# SL869-GL868-Cx.net
KiCad netlist of a schematic drawn in EAGLE
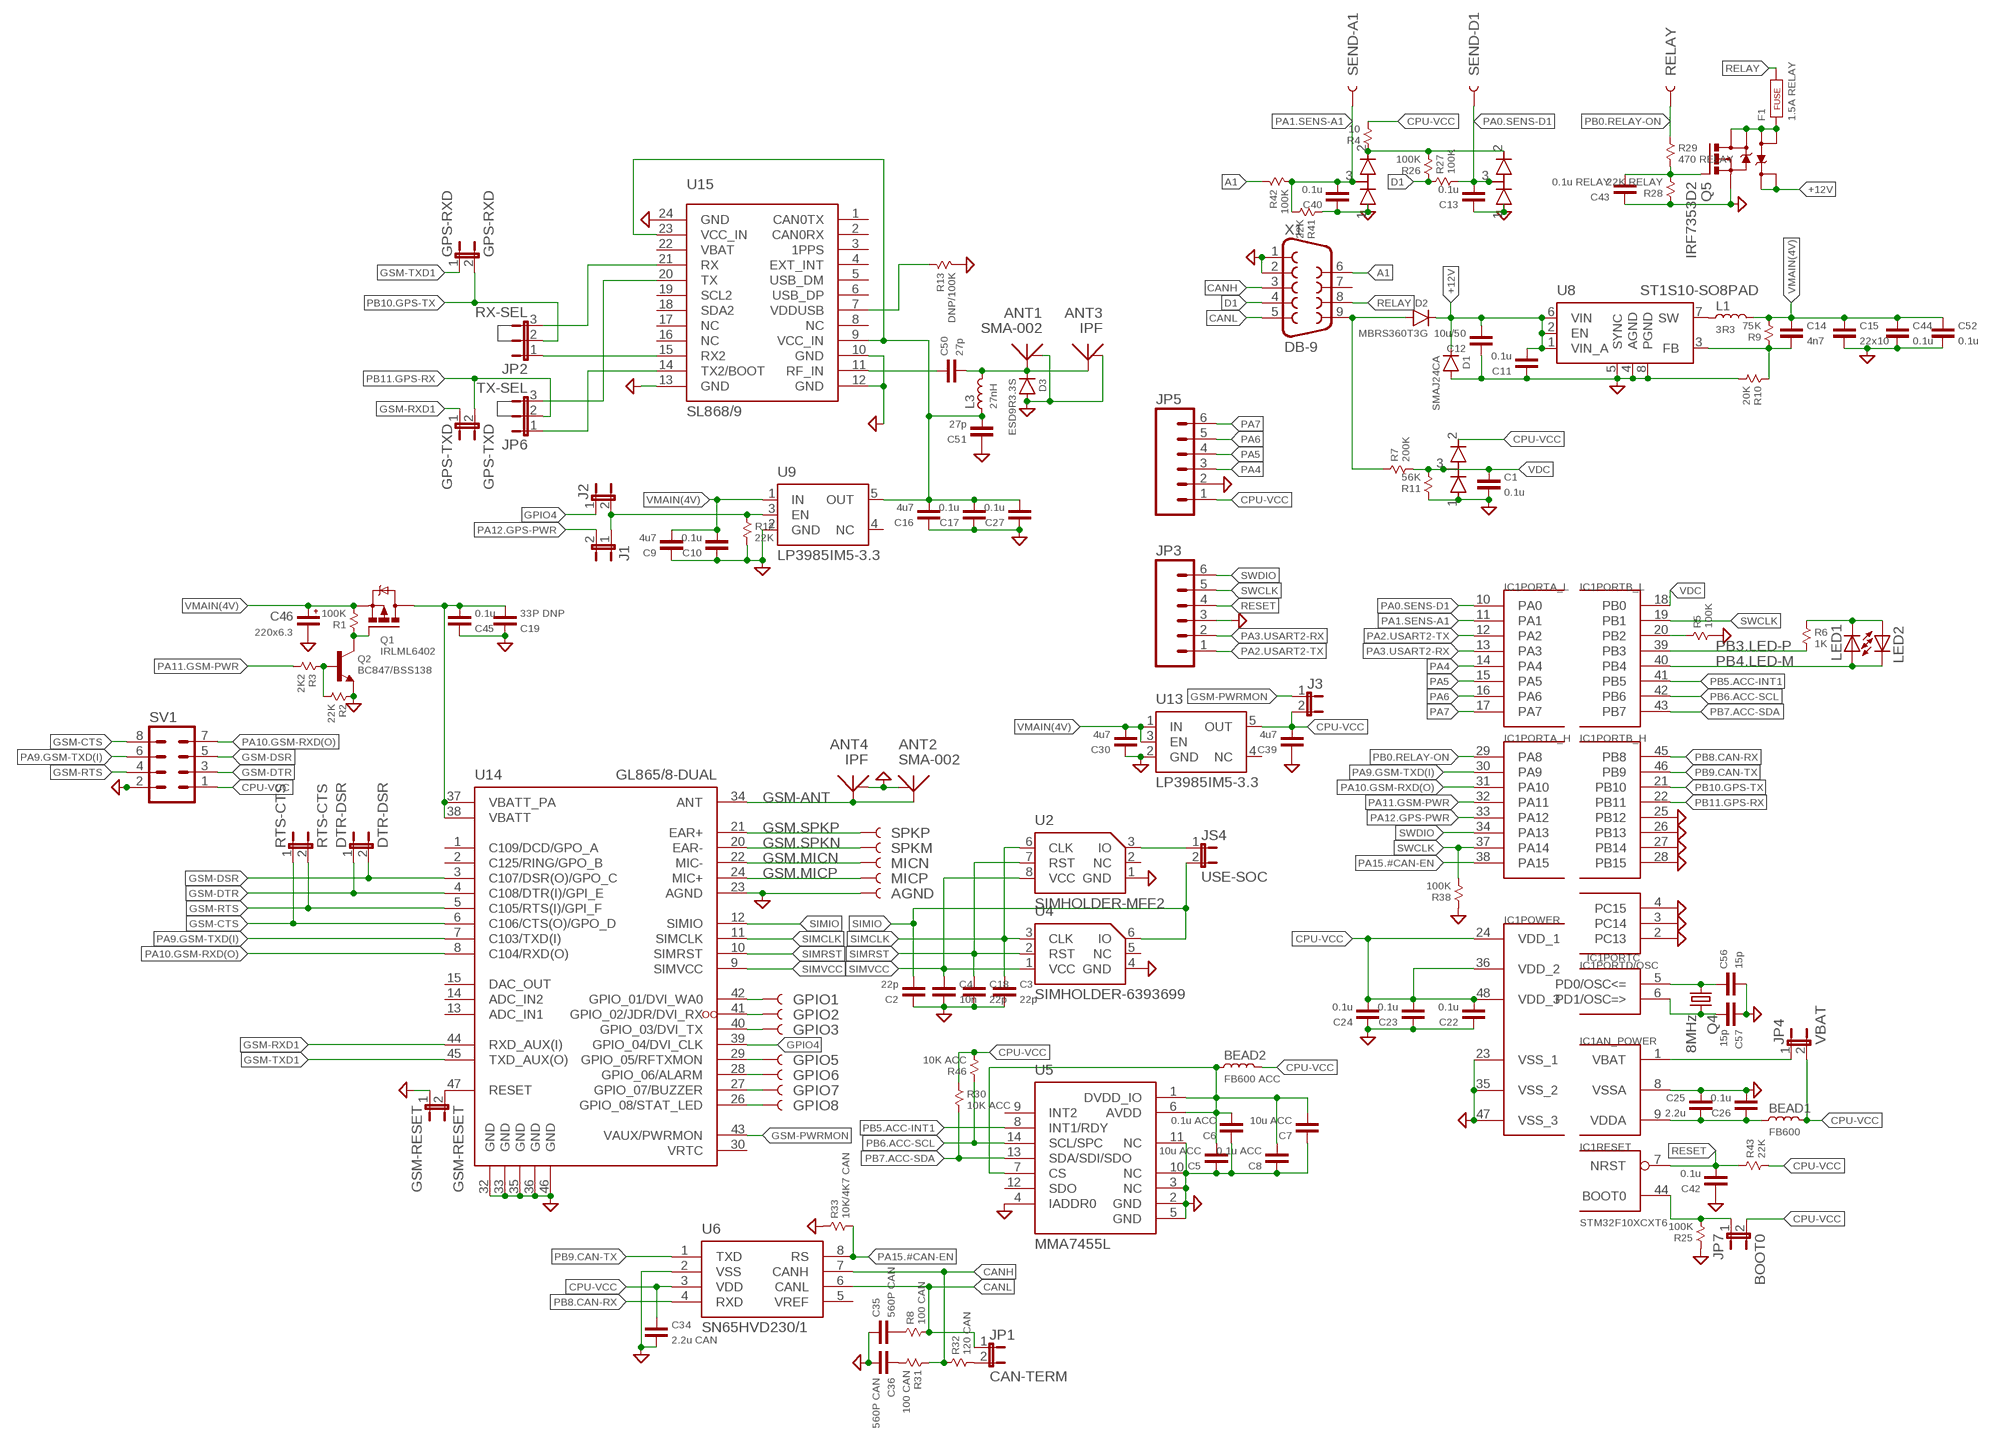
[diagram p0: schematic, sheet 1]

(export (version "E")
  (design (tool "Eeschema 10.0.6"))
  (components
    (comp (ref "AGND")
      (value "TEST-POINT1")
      (footprint "eagle-import:PAD.1X1")
      (libsource (lib "eagle-import") (part "TEST-POINT1"))
    )
    (comp (ref "ANT1")
      (value "SMA-002")
      (footprint "eagle-import:SMA-002")
      (libsource (lib "eagle-import") (part "ANTENNA-SMA-002"))
    )
    (comp (ref "ANT2")
      (value "SMA-002")
      (footprint "eagle-import:SMA-002")
      (libsource (lib "eagle-import") (part "ANTENNA-SMA-002"))
    )
    (comp (ref "ANT3")
      (value "IPF")
      (footprint "eagle-import:MM9329")
      (libsource (lib "eagle-import") (part "ANTENNA-IPF"))
    )
    (comp (ref "ANT4")
      (value "IPF")
      (footprint "eagle-import:MM9329")
      (libsource (lib "eagle-import") (part "ANTENNA-IPF"))
    )
    (comp (ref "BEAD1")
      (value "FB600")
      (footprint "eagle-import:0603")
      (libsource (lib "eagle-import") (part "INDUCTOR-0603"))
    )
    (comp (ref "BEAD2")
      (value "FB600 ACC")
      (footprint "eagle-import:0603")
      (libsource (lib "eagle-import") (part "INDUCTOR-0603"))
    )
    (comp (ref "C1")
      (value "0.1u")
      (footprint "eagle-import:0603")
      (libsource (lib "eagle-import") (part "CAP-0603"))
    )
    (comp (ref "C2")
      (value "22p")
      (footprint "eagle-import:0603")
      (libsource (lib "eagle-import") (part "CAP-0603"))
    )
    (comp (ref "C3")
      (value "22p")
      (footprint "eagle-import:0603")
      (libsource (lib "eagle-import") (part "CAP-0603"))
    )
    (comp (ref "C4")
      (value "10n")
      (footprint "eagle-import:0603")
      (libsource (lib "eagle-import") (part "CAP-0603"))
    )
    (comp (ref "C5")
      (value "10u ACC")
      (footprint "eagle-import:0603")
      (libsource (lib "eagle-import") (part "CAP-0603"))
    )
    (comp (ref "C6")
      (value "0.1u ACC")
      (footprint "eagle-import:0603")
      (libsource (lib "eagle-import") (part "CAP-0603"))
    )
    (comp (ref "C7")
      (value "10u ACC")
      (footprint "eagle-import:0603")
      (libsource (lib "eagle-import") (part "CAP-0603"))
    )
    (comp (ref "C8")
      (value "0.1u ACC")
      (footprint "eagle-import:0603")
      (libsource (lib "eagle-import") (part "CAP-0603"))
    )
    (comp (ref "C9")
      (value "4u7")
      (footprint "eagle-import:0603")
      (libsource (lib "eagle-import") (part "CAP-0603"))
    )
    (comp (ref "C10")
      (value "0.1u")
      (footprint "eagle-import:0603")
      (libsource (lib "eagle-import") (part "CAP-0603"))
    )
    (comp (ref "C11")
      (value "0.1u")
      (footprint "eagle-import:0603")
      (libsource (lib "eagle-import") (part "CAP-0603"))
    )
    (comp (ref "C12")
      (value "10u/50")
      (footprint "eagle-import:1206")
      (libsource (lib "eagle-import") (part "CAP-1206"))
    )
    (comp (ref "C13")
      (value "0.1u")
      (footprint "eagle-import:0603")
      (libsource (lib "eagle-import") (part "CAP-0603"))
    )
    (comp (ref "C14")
      (value "4n7")
      (footprint "eagle-import:0603")
      (libsource (lib "eagle-import") (part "CAP-0603"))
    )
    (comp (ref "C15")
      (value "22x10")
      (footprint "eagle-import:1206")
      (libsource (lib "eagle-import") (part "CAP-1206"))
    )
    (comp (ref "C16")
      (value "4u7")
      (footprint "eagle-import:0603")
      (libsource (lib "eagle-import") (part "CAP-0603"))
    )
    (comp (ref "C17")
      (value "0.1u")
      (footprint "eagle-import:0603")
      (libsource (lib "eagle-import") (part "CAP-0603"))
    )
    (comp (ref "C18")
      (value "22p")
      (footprint "eagle-import:0603")
      (libsource (lib "eagle-import") (part "CAP-0603"))
    )
    (comp (ref "C19")
      (value "33P DNP")
      (footprint "eagle-import:0603")
      (libsource (lib "eagle-import") (part "CAP-0603"))
    )
    (comp (ref "C22")
      (value "0.1u")
      (footprint "eagle-import:0603")
      (libsource (lib "eagle-import") (part "CAP-0603"))
    )
    (comp (ref "C23")
      (value "0.1u")
      (footprint "eagle-import:0603")
      (libsource (lib "eagle-import") (part "CAP-0603"))
    )
    (comp (ref "C24")
      (value "0.1u")
      (footprint "eagle-import:0603")
      (libsource (lib "eagle-import") (part "CAP-0603"))
    )
    (comp (ref "C25")
      (value "2.2u")
      (footprint "eagle-import:0603")
      (libsource (lib "eagle-import") (part "CAP-0603"))
    )
    (comp (ref "C26")
      (value "0.1u")
      (footprint "eagle-import:0603")
      (libsource (lib "eagle-import") (part "CAP-0603"))
    )
    (comp (ref "C27")
      (value "0.1u")
      (footprint "eagle-import:0603")
      (libsource (lib "eagle-import") (part "CAP-0603"))
    )
    (comp (ref "C30")
      (value "4u7")
      (footprint "eagle-import:0603")
      (libsource (lib "eagle-import") (part "CAP-0603"))
    )
    (comp (ref "C34")
      (value "2.2u CAN")
      (footprint "eagle-import:0603")
      (libsource (lib "eagle-import") (part "CAP-0603"))
    )
    (comp (ref "C35")
      (value "560P CAN")
      (footprint "eagle-import:0603")
      (libsource (lib "eagle-import") (part "CAP-0603"))
    )
    (comp (ref "C36")
      (value "560P CAN")
      (footprint "eagle-import:0603")
      (libsource (lib "eagle-import") (part "CAP-0603"))
    )
    (comp (ref "C39")
      (value "4u7")
      (footprint "eagle-import:0603")
      (libsource (lib "eagle-import") (part "CAP-0603"))
    )
    (comp (ref "C40")
      (value "0.1u")
      (footprint "eagle-import:0603")
      (libsource (lib "eagle-import") (part "CAP-0603"))
    )
    (comp (ref "C42")
      (value "0.1u")
      (footprint "eagle-import:0603")
      (libsource (lib "eagle-import") (part "CAP-0603"))
    )
    (comp (ref "C43")
      (value "0.1u RELAY")
      (footprint "eagle-import:0603")
      (libsource (lib "eagle-import") (part "CAP-0603"))
    )
    (comp (ref "C44")
      (value "0.1u")
      (footprint "eagle-import:0603")
      (libsource (lib "eagle-import") (part "CAP-0603"))
    )
    (comp (ref "C45")
      (value "0.1u")
      (footprint "eagle-import:0603")
      (libsource (lib "eagle-import") (part "CAP-0603"))
    )
    (comp (ref "C46")
      (value "220x6.3")
      (footprint "eagle-import:CT7343")
      (libsource (lib "eagle-import") (part "CAP-POL-7343"))
    )
    (comp (ref "C50")
      (value "27p")
      (footprint "eagle-import:0603")
      (libsource (lib "eagle-import") (part "CAP-0603"))
    )
    (comp (ref "C51")
      (value "27p")
      (footprint "eagle-import:0603")
      (libsource (lib "eagle-import") (part "CAP-0603"))
    )
    (comp (ref "C52")
      (value "0.1u")
      (footprint "eagle-import:0603")
      (libsource (lib "eagle-import") (part "CAP-0603"))
    )
    (comp (ref "C56")
      (value "15p")
      (footprint "eagle-import:0603")
      (libsource (lib "eagle-import") (part "CAP-0603"))
    )
    (comp (ref "C57")
      (value "15p")
      (footprint "eagle-import:0603")
      (libsource (lib "eagle-import") (part "CAP-0603"))
    )
    (comp (ref "D1")
      (value "SMAJ24CA")
      (footprint "eagle-import:SMA")
      (libsource (lib "eagle-import") (part "DIODE-SMA"))
    )
    (comp (ref "D2")
      (value "MBRS360T3G")
      (footprint "eagle-import:SMC")
      (libsource (lib "eagle-import") (part "DIODE-SMC"))
    )
    (comp (ref "D3")
      (value "ESD9R3.3S")
      (footprint "eagle-import:SOD-923")
      (libsource (lib "eagle-import") (part "DIODE-ESD9"))
    )
    (comp (ref "D4")
      (value "BAV99")
      (footprint "eagle-import:SOT-23")
      (libsource (lib "eagle-import") (part "BAV99"))
    )
    (comp (ref "D5")
      (value "BAV99")
      (footprint "eagle-import:SOT-23")
      (libsource (lib "eagle-import") (part "BAV99"))
    )
    (comp (ref "D14")
      (value "BAV99")
      (footprint "eagle-import:SOT-23")
      (libsource (lib "eagle-import") (part "BAV99"))
    )
    (comp (ref "DTR-DSR")
      (value "DTR-DSR")
      (footprint "eagle-import:SJ_2S-NO")
      (libsource (lib "eagle-import") (part "JUMPER-2SMD-NO"))
    )
    (comp (ref "F1")
      (value "1.5A RELAY")
      (footprint "eagle-import:1812")
      (libsource (lib "eagle-import") (part "FUSE"))
    )
    (comp (ref "GPIO1")
      (value "TEST-POINT1")
      (footprint "eagle-import:PAD.1X1")
      (libsource (lib "eagle-import") (part "TEST-POINT1"))
    )
    (comp (ref "GPIO2")
      (value "TEST-POINT1")
      (footprint "eagle-import:PAD.1X1")
      (libsource (lib "eagle-import") (part "TEST-POINT1"))
    )
    (comp (ref "GPIO3")
      (value "TEST-POINT1")
      (footprint "eagle-import:PAD.1X1")
      (libsource (lib "eagle-import") (part "TEST-POINT1"))
    )
    (comp (ref "GPIO5")
      (value "TEST-POINT1")
      (footprint "eagle-import:PAD.1X1")
      (libsource (lib "eagle-import") (part "TEST-POINT1"))
    )
    (comp (ref "GPIO6")
      (value "TEST-POINT1")
      (footprint "eagle-import:PAD.1X1")
      (libsource (lib "eagle-import") (part "TEST-POINT1"))
    )
    (comp (ref "GPIO7")
      (value "TEST-POINT1")
      (footprint "eagle-import:PAD.1X1")
      (libsource (lib "eagle-import") (part "TEST-POINT1"))
    )
    (comp (ref "GPIO8")
      (value "TEST-POINT1")
      (footprint "eagle-import:PAD.1X1")
      (libsource (lib "eagle-import") (part "TEST-POINT1"))
    )
    (comp (ref "GPS-RXD")
      (value "GPS-RXD")
      (footprint "eagle-import:SJ_2S-NO")
      (libsource (lib "eagle-import") (part "JUMPER-2SMD-NO"))
    )
    (comp (ref "GPS-TXD")
      (value "GPS-TXD")
      (footprint "eagle-import:SJ_2S-NO")
      (libsource (lib "eagle-import") (part "JUMPER-2SMD-NO"))
    )
    (comp (ref "GSM-RESET")
      (value "GSM-RESET")
      (footprint "eagle-import:SJ_2S-NO")
      (libsource (lib "eagle-import") (part "JUMPER-2SMD-NO"))
    )
    (comp (ref "IC1")
      (value "STM32F10XCXT6")
      (footprint "eagle-import:TQFP48")
      (libsource (lib "eagle-import") (part "STM32F10XCXT6"))
    )
    (comp (ref "J1")
      (value "JUMPER-2SMD-NO")
      (footprint "eagle-import:SJ_2S-NO")
      (libsource (lib "eagle-import") (part "JUMPER-2SMD-NO"))
    )
    (comp (ref "J2")
      (value "JUMPER-2SMD-NO")
      (footprint "eagle-import:SJ_2S-NO")
      (libsource (lib "eagle-import") (part "JUMPER-2SMD-NO"))
    )
    (comp (ref "J3")
      (value "JUMPER-2SMD-NO")
      (footprint "eagle-import:SJ_2S-NO")
      (libsource (lib "eagle-import") (part "JUMPER-2SMD-NO"))
    )
    (comp (ref "JP1")
      (value "CAN-TERM")
      (footprint "eagle-import:SJ_2S-NO")
      (libsource (lib "eagle-import") (part "JUMPER-2SMD-NO"))
    )
    (comp (ref "JP2")
      (value "RX-SEL")
      (footprint "eagle-import:SJ_3")
      (libsource (lib "eagle-import") (part "JUMPER-3SMD"))
    )
    (comp (ref "JP3")
      (value "M06SIP")
      (footprint "eagle-import:1X06")
      (libsource (lib "eagle-import") (part "M06SIP"))
    )
    (comp (ref "JP4")
      (value "VBAT")
      (footprint "eagle-import:SJ_2S-NO")
      (libsource (lib "eagle-import") (part "JUMPER-2SMD-NO"))
    )
    (comp (ref "JP5")
      (value "M06SIP")
      (footprint "eagle-import:1X06")
      (libsource (lib "eagle-import") (part "M06SIP"))
    )
    (comp (ref "JP6")
      (value "TX-SEL")
      (footprint "eagle-import:SJ_3")
      (libsource (lib "eagle-import") (part "JUMPER-3SMD"))
    )
    (comp (ref "JP7")
      (value "BOOT0")
      (footprint "eagle-import:SJ_2S-NO")
      (libsource (lib "eagle-import") (part "JUMPER-2SMD-NO"))
    )
    (comp (ref "JS4")
      (value "USE-SOC")
      (footprint "eagle-import:SJ_2S-NO")
      (libsource (lib "eagle-import") (part "JUMPER-2SMD-NO"))
    )
    (comp (ref "L1")
      (value "3R3")
      (footprint "eagle-import:CDRH6D38NP")
      (libsource (lib "eagle-import") (part "INDUCTOR-CDRH6D38NP"))
    )
    (comp (ref "L3")
      (value "27nH")
      (footprint "eagle-import:0603")
      (libsource (lib "eagle-import") (part "INDUCTOR-0603"))
    )
    (comp (ref "LED1")
      (value "LED3MM")
      (footprint "eagle-import:LED3MM")
      (libsource (lib "eagle-import") (part "LED3MM"))
    )
    (comp (ref "LED2")
      (value "LED3MM")
      (footprint "eagle-import:LED3MM")
      (libsource (lib "eagle-import") (part "LED3MM"))
    )
    (comp (ref "MICN")
      (value "TEST-POINT1")
      (footprint "eagle-import:PAD.1X1")
      (libsource (lib "eagle-import") (part "TEST-POINT1"))
    )
    (comp (ref "MICP")
      (value "TEST-POINT1")
      (footprint "eagle-import:PAD.1X1")
      (libsource (lib "eagle-import") (part "TEST-POINT1"))
    )
    (comp (ref "Q1")
      (value "IRLML6402")
      (footprint "eagle-import:SOT-23")
      (libsource (lib "eagle-import") (part "IRLML6402"))
    )
    (comp (ref "Q2")
      (value "BC847/BSS138")
      (footprint "eagle-import:SOT-23")
      (libsource (lib "eagle-import") (part "NPNBC847"))
    )
    (comp (ref "Q4")
      (value "8MHz")
      (footprint "eagle-import:HC49U-V")
      (libsource (lib "eagle-import") (part "CRYSTALHC49UV"))
    )
    (comp (ref "Q5")
      (value "IRF7353D2")
      (footprint "eagle-import:SO08")
      (libsource (lib "eagle-import") (part "IRF7353D2"))
    )
    (comp (ref "R1")
      (value "100K")
      (footprint "eagle-import:0603")
      (libsource (lib "eagle-import") (part "RESISTOR-0603"))
    )
    (comp (ref "R2")
      (value "22K")
      (footprint "eagle-import:0603")
      (libsource (lib "eagle-import") (part "RESISTOR-0603"))
    )
    (comp (ref "R3")
      (value "2K2")
      (footprint "eagle-import:0603")
      (libsource (lib "eagle-import") (part "RESISTOR-0603"))
    )
    (comp (ref "R4")
      (value "10")
      (footprint "eagle-import:0603")
      (libsource (lib "eagle-import") (part "RESISTOR-0603"))
    )
    (comp (ref "R5")
      (value "100K")
      (footprint "eagle-import:0603")
      (libsource (lib "eagle-import") (part "RESISTOR-0603"))
    )
    (comp (ref "R6")
      (value "1K")
      (footprint "eagle-import:0603")
      (libsource (lib "eagle-import") (part "RESISTOR-0603"))
    )
    (comp (ref "R7")
      (value "200K")
      (footprint "eagle-import:0603")
      (libsource (lib "eagle-import") (part "RESISTOR-0603"))
    )
    (comp (ref "R8")
      (value "100 CAN")
      (footprint "eagle-import:0603")
      (libsource (lib "eagle-import") (part "RESISTOR-0603"))
    )
    (comp (ref "R9")
      (value "75K")
      (footprint "eagle-import:0603")
      (libsource (lib "eagle-import") (part "RESISTOR-0603"))
    )
    (comp (ref "R10")
      (value "20K")
      (footprint "eagle-import:0603")
      (libsource (lib "eagle-import") (part "RESISTOR-0603"))
    )
    (comp (ref "R11")
      (value "56K")
      (footprint "eagle-import:0603")
      (libsource (lib "eagle-import") (part "RESISTOR-0603"))
    )
    (comp (ref "R12")
      (value "22K")
      (footprint "eagle-import:0603")
      (libsource (lib "eagle-import") (part "RESISTOR-0603"))
    )
    (comp (ref "R13")
      (value "DNP/100K")
      (footprint "eagle-import:0603")
      (libsource (lib "eagle-import") (part "RESISTOR-0603"))
    )
    (comp (ref "R25")
      (value "100K")
      (footprint "eagle-import:0603")
      (libsource (lib "eagle-import") (part "RESISTOR-0603"))
    )
    (comp (ref "R26")
      (value "100K")
      (footprint "eagle-import:0603")
      (libsource (lib "eagle-import") (part "RESISTOR-0603"))
    )
    (comp (ref "R27")
      (value "100K")
      (footprint "eagle-import:0603")
      (libsource (lib "eagle-import") (part "RESISTOR-0603"))
    )
    (comp (ref "R28")
      (value "22K RELAY")
      (footprint "eagle-import:0603")
      (libsource (lib "eagle-import") (part "RESISTOR-0603"))
    )
    (comp (ref "R29")
      (value "470 RELAY")
      (footprint "eagle-import:0603")
      (libsource (lib "eagle-import") (part "RESISTOR-0603"))
    )
    (comp (ref "R30")
      (value "10K ACC")
      (footprint "eagle-import:0603")
      (libsource (lib "eagle-import") (part "RESISTOR-0603"))
    )
    (comp (ref "R31")
      (value "100 CAN")
      (footprint "eagle-import:0603")
      (libsource (lib "eagle-import") (part "RESISTOR-0603"))
    )
    (comp (ref "R32")
      (value "120 CAN")
      (footprint "eagle-import:0603")
      (libsource (lib "eagle-import") (part "RESISTOR-0603"))
    )
    (comp (ref "R33")
      (value "10K/4K7 CAN")
      (footprint "eagle-import:0603")
      (libsource (lib "eagle-import") (part "RESISTOR-0603"))
    )
    (comp (ref "R38")
      (value "100K")
      (footprint "eagle-import:0603")
      (libsource (lib "eagle-import") (part "RESISTOR-0603"))
    )
    (comp (ref "R41")
      (value "22K")
      (footprint "eagle-import:0603")
      (libsource (lib "eagle-import") (part "RESISTOR-0603"))
    )
    (comp (ref "R42")
      (value "100K")
      (footprint "eagle-import:0603")
      (libsource (lib "eagle-import") (part "RESISTOR-0603"))
    )
    (comp (ref "R43")
      (value "22K")
      (footprint "eagle-import:0603")
      (libsource (lib "eagle-import") (part "RESISTOR-0603"))
    )
    (comp (ref "R46")
      (value "10K ACC")
      (footprint "eagle-import:0603")
      (libsource (lib "eagle-import") (part "RESISTOR-0603"))
    )
    (comp (ref "RELAY")
      (value "TEST-POINT1")
      (footprint "eagle-import:PAD.1X1")
      (libsource (lib "eagle-import") (part "TEST-POINT1"))
    )
    (comp (ref "RTS-CTS")
      (value "RTS-CTS")
      (footprint "eagle-import:SJ_2S-NO")
      (libsource (lib "eagle-import") (part "JUMPER-2SMD-NO"))
    )
    (comp (ref "SEND-A1")
      (value "TEST-POINT1")
      (footprint "eagle-import:PAD.1X1")
      (libsource (lib "eagle-import") (part "TEST-POINT1"))
    )
    (comp (ref "SEND-D1")
      (value "TEST-POINT1")
      (footprint "eagle-import:PAD.1X1")
      (libsource (lib "eagle-import") (part "TEST-POINT1"))
    )
    (comp (ref "SPKM")
      (value "TEST-POINT1")
      (footprint "eagle-import:PAD.1X1")
      (libsource (lib "eagle-import") (part "TEST-POINT1"))
    )
    (comp (ref "SPKP")
      (value "TEST-POINT1")
      (footprint "eagle-import:PAD.1X1")
      (libsource (lib "eagle-import") (part "TEST-POINT1"))
    )
    (comp (ref "SV1")
      (value "MA04-2")
      (footprint "eagle-import:MA04-2")
      (libsource (lib "eagle-import") (part "MA04-2"))
    )
    (comp (ref "U2")
      (value "SIMHOLDER-MFF2")
      (footprint "eagle-import:MFF2")
      (libsource (lib "eagle-import") (part "SIMHOLDER-MFF2"))
    )
    (comp (ref "U4")
      (value "SIMHOLDER-6393699")
      (footprint "eagle-import:6393699-1")
      (libsource (lib "eagle-import") (part "SIMHOLDER-6393699"))
    )
    (comp (ref "U5")
      (value "MMA7455L")
      (footprint "eagle-import:LGA14")
      (libsource (lib "eagle-import") (part "MMA7455L"))
    )
    (comp (ref "U6")
      (value "SN65HVD230/1")
      (footprint "eagle-import:SO08")
      (libsource (lib "eagle-import") (part "MCP2551"))
    )
    (comp (ref "U8")
      (value "ST1S10-SO8PAD")
      (footprint "eagle-import:SO08-EPAD")
      (libsource (lib "eagle-import") (part "ST1S10-SO8PAD"))
    )
    (comp (ref "U9")
      (value "LP3985IM5-3.3")
      (footprint "eagle-import:SOT23-5")
      (libsource (lib "eagle-import") (part "TPS73033"))
    )
    (comp (ref "U13")
      (value "LP3985IM5-3.3")
      (footprint "eagle-import:SOT23-5")
      (libsource (lib "eagle-import") (part "TPS73033"))
    )
    (comp (ref "U14")
      (value "GL865/8-DUAL")
      (footprint "eagle-import:GL865_8-DUAL")
      (libsource (lib "eagle-import") (part "GL865/8-DUAL"))
    )
    (comp (ref "U15")
      (value "SL868/9")
      (footprint "eagle-import:SL868_9")
      (libsource (lib "eagle-import") (part "SL868/9"))
    )
    (comp (ref "X1")
      (value "DB-9")
      (footprint "eagle-import:DB9")
      (libsource (lib "eagle-import") (part "DB9"))
    )
  )
  (nets
    (net (code "1") (name "+12V") (class "Default")
      (node (ref "C11") (pin "1") (pinfunction "1_1") (pintype "passive"))
      (node (ref "C12") (pin "1") (pinfunction "1_1") (pintype "passive"))
      (node (ref "D1") (pin "P$1") (pinfunction "C_P$1") (pintype "passive"))
      (node (ref "D2") (pin "P$1") (pinfunction "C_P$1") (pintype "passive"))
      (node (ref "Q5") (pin "7") (pinfunction "K_7") (pintype "passive"))
      (node (ref "Q5") (pin "8") (pinfunction "K_8") (pintype "passive"))
      (node (ref "U8") (pin "1") (pinfunction "VIN_A_1") (pintype "passive"))
      (node (ref "U8") (pin "2") (pinfunction "EN_2") (pintype "passive"))
      (node (ref "U8") (pin "6") (pinfunction "VIN_6") (pintype "passive"))
    )
    (net (code "2") (name "/GSM-ANT") (class "Default")
      (node (ref "ANT2") (pin "A") (pinfunction "ANT_A") (pintype "passive"))
      (node (ref "ANT4") (pin "1") (pinfunction "ANT_1") (pintype "passive"))
      (node (ref "U14") (pin "34") (pinfunction "ANT_34") (pintype "passive"))
    )
    (net (code "3") (name "/GSM.MICN") (class "Default")
      (node (ref "MICN") (pin "P$1") (pinfunction "1_P$1") (pintype "bidirectional"))
      (node (ref "U14") (pin "22") (pinfunction "MIC-_22") (pintype "passive"))
    )
    (net (code "4") (name "/GSM.MICP") (class "Default")
      (node (ref "MICP") (pin "P$1") (pinfunction "1_P$1") (pintype "bidirectional"))
      (node (ref "U14") (pin "24") (pinfunction "MIC+_24") (pintype "passive"))
    )
    (net (code "5") (name "/GSM.SPKN") (class "Default")
      (node (ref "SPKM") (pin "P$1") (pinfunction "1_P$1") (pintype "bidirectional"))
      (node (ref "U14") (pin "20") (pinfunction "EAR-_20") (pintype "passive"))
    )
    (net (code "6") (name "/GSM.SPKP") (class "Default")
      (node (ref "SPKP") (pin "P$1") (pinfunction "1_P$1") (pintype "bidirectional"))
      (node (ref "U14") (pin "21") (pinfunction "EAR+_21") (pintype "passive"))
    )
    (net (code "7") (name "/PB3.LED-P") (class "Default")
      (node (ref "IC1") (pin "39") (pinfunction "PB3_39") (pintype "bidirectional"))
      (node (ref "R6") (pin "2") (pinfunction "2_2") (pintype "passive"))
    )
    (net (code "8") (name "/PB4.LED-M") (class "Default")
      (node (ref "IC1") (pin "40") (pinfunction "PB4_40") (pintype "bidirectional"))
      (node (ref "LED1") (pin "A") (pinfunction "A_A") (pintype "passive"))
      (node (ref "LED2") (pin "K") (pinfunction "C_K") (pintype "passive"))
    )
    (net (code "9") (name "A1") (class "Default")
      (node (ref "R42") (pin "1") (pinfunction "1_1") (pintype "passive"))
      (node (ref "X1") (pin "6") (pinfunction "6_6") (pintype "passive"))
    )
    (net (code "10") (name "CANH") (class "Default")
      (node (ref "R31") (pin "1") (pinfunction "1_1") (pintype "passive"))
      (node (ref "R32") (pin "1") (pinfunction "1_1") (pintype "passive"))
      (node (ref "U6") (pin "7") (pinfunction "CANH_7") (pintype "bidirectional"))
      (node (ref "X1") (pin "3") (pinfunction "3_3") (pintype "passive"))
    )
    (net (code "11") (name "CANL") (class "Default")
      (node (ref "JP1") (pin "1") (pinfunction "1_1") (pintype "passive"))
      (node (ref "R8") (pin "2") (pinfunction "2_2") (pintype "passive"))
      (node (ref "U6") (pin "6") (pinfunction "CANL_6") (pintype "bidirectional"))
      (node (ref "X1") (pin "5") (pinfunction "5_5") (pintype "passive"))
    )
    (net (code "12") (name "CPU-VCC") (class "Default")
      (node (ref "BEAD1") (pin "2") (pinfunction "2_2") (pintype "passive"))
      (node (ref "BEAD2") (pin "2") (pinfunction "2_2") (pintype "passive"))
      (node (ref "C22") (pin "1") (pinfunction "1_1") (pintype "passive"))
      (node (ref "C23") (pin "1") (pinfunction "1_1") (pintype "passive"))
      (node (ref "C24") (pin "1") (pinfunction "1_1") (pintype "passive"))
      (node (ref "C34") (pin "2") (pinfunction "2_2") (pintype "passive"))
      (node (ref "C39") (pin "1") (pinfunction "1_1") (pintype "passive"))
      (node (ref "D5") (pin "2") (pinfunction "+_2") (pintype "passive"))
      (node (ref "IC1") (pin "24") (pinfunction "VDD_1_24") (pintype "power_in"))
      (node (ref "IC1") (pin "36") (pinfunction "VDD_2_36") (pintype "power_in"))
      (node (ref "IC1") (pin "48") (pinfunction "VDD_3_48") (pintype "power_in"))
      (node (ref "J3") (pin "2") (pinfunction "2_2") (pintype "passive"))
      (node (ref "JP4") (pin "2") (pinfunction "2_2") (pintype "passive"))
      (node (ref "JP5") (pin "1") (pinfunction "1_1") (pintype "passive"))
      (node (ref "JP7") (pin "2") (pinfunction "2_2") (pintype "passive"))
      (node (ref "R30") (pin "1") (pinfunction "1_1") (pintype "passive"))
      (node (ref "R4") (pin "2") (pinfunction "2_2") (pintype "passive"))
      (node (ref "R43") (pin "2") (pinfunction "2_2") (pintype "passive"))
      (node (ref "R46") (pin "2") (pinfunction "2_2") (pintype "passive"))
      (node (ref "SV1") (pin "1") (pinfunction "1_1") (pintype "passive"))
      (node (ref "U13") (pin "5") (pinfunction "OUT_5") (pintype "passive"))
      (node (ref "U6") (pin "3") (pinfunction "VDD_3") (pintype "bidirectional"))
    )
    (net (code "13") (name "D1") (class "Default")
      (node (ref "R26") (pin "1") (pinfunction "1_1") (pintype "passive"))
      (node (ref "R27") (pin "1") (pinfunction "1_1") (pintype "passive"))
      (node (ref "X1") (pin "4") (pinfunction "4_4") (pintype "passive"))
    )
    (net (code "14") (name "GND") (class "Default")
      (node (ref "AGND") (pin "P$1") (pinfunction "1_P$1") (pintype "bidirectional"))
      (node (ref "ANT1") (pin "GND@1") (pinfunction "GND_GND@1") (pintype "power_in"))
      (node (ref "ANT2") (pin "GND@1") (pinfunction "GND_GND@1") (pintype "power_in"))
      (node (ref "ANT3") (pin "2") (pinfunction "GND_2") (pintype "power_in"))
      (node (ref "ANT4") (pin "2") (pinfunction "GND_2") (pintype "power_in"))
      (node (ref "C1") (pin "1") (pinfunction "1_1") (pintype "passive"))
      (node (ref "C10") (pin "2") (pinfunction "2_2") (pintype "passive"))
      (node (ref "C11") (pin "2") (pinfunction "2_2") (pintype "passive"))
      (node (ref "C12") (pin "2") (pinfunction "2_2") (pintype "passive"))
      (node (ref "C13") (pin "2") (pinfunction "2_2") (pintype "passive"))
      (node (ref "C15") (pin "1") (pinfunction "1_1") (pintype "passive"))
      (node (ref "C16") (pin "2") (pinfunction "2_2") (pintype "passive"))
      (node (ref "C17") (pin "2") (pinfunction "2_2") (pintype "passive"))
      (node (ref "C18") (pin "1") (pinfunction "1_1") (pintype "passive"))
      (node (ref "C19") (pin "2") (pinfunction "2_2") (pintype "passive"))
      (node (ref "C2") (pin "2") (pinfunction "2_2") (pintype "passive"))
      (node (ref "C22") (pin "2") (pinfunction "2_2") (pintype "passive"))
      (node (ref "C23") (pin "2") (pinfunction "2_2") (pintype "passive"))
      (node (ref "C24") (pin "2") (pinfunction "2_2") (pintype "passive"))
      (node (ref "C25") (pin "2") (pinfunction "2_2") (pintype "passive"))
      (node (ref "C26") (pin "1") (pinfunction "1_1") (pintype "passive"))
      (node (ref "C27") (pin "2") (pinfunction "2_2") (pintype "passive"))
      (node (ref "C3") (pin "1") (pinfunction "1_1") (pintype "passive"))
      (node (ref "C30") (pin "2") (pinfunction "2_2") (pintype "passive"))
      (node (ref "C34") (pin "1") (pinfunction "1_1") (pintype "passive"))
      (node (ref "C35") (pin "2") (pinfunction "2_2") (pintype "passive"))
      (node (ref "C36") (pin "1") (pinfunction "1_1") (pintype "passive"))
      (node (ref "C39") (pin "2") (pinfunction "2_2") (pintype "passive"))
      (node (ref "C4") (pin "1") (pinfunction "1_1") (pintype "passive"))
      (node (ref "C40") (pin "2") (pinfunction "2_2") (pintype "passive"))
      (node (ref "C42") (pin "2") (pinfunction "2_2") (pintype "passive"))
      (node (ref "C43") (pin "2") (pinfunction "2_2") (pintype "passive"))
      (node (ref "C44") (pin "1") (pinfunction "1_1") (pintype "passive"))
      (node (ref "C45") (pin "2") (pinfunction "2_2") (pintype "passive"))
      (node (ref "C46") (pin "-") (pinfunction "-_-") (pintype "passive"))
      (node (ref "C5") (pin "2") (pinfunction "2_2") (pintype "passive"))
      (node (ref "C51") (pin "2") (pinfunction "2_2") (pintype "passive"))
      (node (ref "C52") (pin "1") (pinfunction "1_1") (pintype "passive"))
      (node (ref "C56") (pin "1") (pinfunction "1_1") (pintype "passive"))
      (node (ref "C57") (pin "2") (pinfunction "2_2") (pintype "passive"))
      (node (ref "C6") (pin "2") (pinfunction "2_2") (pintype "passive"))
      (node (ref "C7") (pin "2") (pinfunction "2_2") (pintype "passive"))
      (node (ref "C8") (pin "2") (pinfunction "2_2") (pintype "passive"))
      (node (ref "C9") (pin "2") (pinfunction "2_2") (pintype "passive"))
      (node (ref "D1") (pin "P$2") (pinfunction "A_P$2") (pintype "passive"))
      (node (ref "D14") (pin "1") (pinfunction "-_1") (pintype "passive"))
      (node (ref "D3") (pin "2") (pinfunction "A_2") (pintype "passive"))
      (node (ref "D4") (pin "1") (pinfunction "-_1") (pintype "passive"))
      (node (ref "D5") (pin "1") (pinfunction "-_1") (pintype "passive"))
      (node (ref "GSM-RESET") (pin "1") (pinfunction "1_1") (pintype "passive"))
      (node (ref "IC1") (pin "2") (pinfunction "PC13_2") (pintype "bidirectional"))
      (node (ref "IC1") (pin "23") (pinfunction "VSS_1_23") (pintype "power_in"))
      (node (ref "IC1") (pin "25") (pinfunction "PB12_25") (pintype "bidirectional"))
      (node (ref "IC1") (pin "26") (pinfunction "PB13_26") (pintype "bidirectional"))
      (node (ref "IC1") (pin "27") (pinfunction "PB14_27") (pintype "bidirectional"))
      (node (ref "IC1") (pin "28") (pinfunction "PB15_28") (pintype "bidirectional"))
      (node (ref "IC1") (pin "3") (pinfunction "PC14_3") (pintype "bidirectional"))
      (node (ref "IC1") (pin "35") (pinfunction "VSS_2_35") (pintype "power_in"))
      (node (ref "IC1") (pin "4") (pinfunction "PC15_4") (pintype "bidirectional"))
      (node (ref "IC1") (pin "47") (pinfunction "VSS_3_47") (pintype "power_in"))
      (node (ref "IC1") (pin "8") (pinfunction "VSSA_8") (pintype "power_in"))
      (node (ref "JP3") (pin "3") (pinfunction "3_3") (pintype "passive"))
      (node (ref "JP5") (pin "2") (pinfunction "2_2") (pintype "passive"))
      (node (ref "Q2") (pin "2") (pinfunction "E_2") (pintype "passive"))
      (node (ref "Q5") (pin "3") (pinfunction "S_3") (pintype "passive"))
      (node (ref "R10") (pin "2") (pinfunction "2_2") (pintype "passive"))
      (node (ref "R11") (pin "1") (pinfunction "1_1") (pintype "passive"))
      (node (ref "R12") (pin "2") (pinfunction "2_2") (pintype "passive"))
      (node (ref "R13") (pin "2") (pinfunction "2_2") (pintype "passive"))
      (node (ref "R2") (pin "1") (pinfunction "1_1") (pintype "passive"))
      (node (ref "R25") (pin "1") (pinfunction "1_1") (pintype "passive"))
      (node (ref "R28") (pin "1") (pinfunction "1_1") (pintype "passive"))
      (node (ref "R33") (pin "1") (pinfunction "1_1") (pintype "passive"))
      (node (ref "R38") (pin "1") (pinfunction "1_1") (pintype "passive"))
      (node (ref "R41") (pin "1") (pinfunction "1_1") (pintype "passive"))
      (node (ref "R5") (pin "2") (pinfunction "2_2") (pintype "passive"))
      (node (ref "SV1") (pin "2") (pinfunction "2_2") (pintype "passive"))
      (node (ref "U13") (pin "2") (pinfunction "GND_2") (pintype "power_in"))
      (node (ref "U14") (pin "23") (pinfunction "AGND_23") (pintype "passive"))
      (node (ref "U14") (pin "32") (pinfunction "GND_32") (pintype "power_in"))
      (node (ref "U14") (pin "33") (pinfunction "GND_33") (pintype "power_in"))
      (node (ref "U14") (pin "35") (pinfunction "GND_35") (pintype "power_in"))
      (node (ref "U14") (pin "36") (pinfunction "GND_36") (pintype "power_in"))
      (node (ref "U14") (pin "46") (pinfunction "GND_46") (pintype "power_in"))
      (node (ref "U15") (pin "10") (pinfunction "GND_10") (pintype "power_in"))
      (node (ref "U15") (pin "12") (pinfunction "GND_12") (pintype "power_in"))
      (node (ref "U15") (pin "13") (pinfunction "GND_13") (pintype "power_in"))
      (node (ref "U15") (pin "24") (pinfunction "GND_24") (pintype "power_in"))
      (node (ref "U2") (pin "1") (pinfunction "GND_1") (pintype "power_in"))
      (node (ref "U4") (pin "4") (pinfunction "GND_4") (pintype "power_in"))
      (node (ref "U5") (pin "10") (pinfunction "NC_10") (pintype "passive"))
      (node (ref "U5") (pin "11") (pinfunction "NC_11") (pintype "passive"))
      (node (ref "U5") (pin "2") (pinfunction "GND_2") (pintype "power_in"))
      (node (ref "U5") (pin "3") (pinfunction "NC_3") (pintype "passive"))
      (node (ref "U5") (pin "4") (pinfunction "IADDR0_4") (pintype "input"))
      (node (ref "U5") (pin "5") (pinfunction "GND_5") (pintype "power_in"))
      (node (ref "U6") (pin "2") (pinfunction "VSS_2") (pintype "bidirectional"))
      (node (ref "U8") (pin "4") (pinfunction "AGND_4") (pintype "passive"))
      (node (ref "U8") (pin "5") (pinfunction "SYNC_5") (pintype "passive"))
      (node (ref "U8") (pin "8") (pinfunction "PGND_8") (pintype "power_in"))
      (node (ref "U9") (pin "2") (pinfunction "GND_2") (pintype "power_in"))
      (node (ref "X1") (pin "1") (pinfunction "1_1") (pintype "passive"))
      (node (ref "X1") (pin "2") (pinfunction "2_2") (pintype "passive"))
    )
    (net (code "15") (name "GPIO4") (class "Default")
      (node (ref "J2") (pin "1") (pinfunction "1_1") (pintype "passive"))
      (node (ref "U14") (pin "39") (pinfunction "GPIO_04/DVI_CLK_39") (pintype "bidirectional"))
    )
    (net (code "16") (name "GSM-CTS") (class "Default")
      (node (ref "RTS-CTS") (pin "1") (pinfunction "1_1") (pintype "passive"))
      (node (ref "SV1") (pin "8") (pinfunction "8_8") (pintype "passive"))
      (node (ref "U14") (pin "6") (pinfunction "C106/CTS(O)/GPO_D_6") (pintype "output"))
    )
    (net (code "17") (name "GSM-DSR") (class "Default")
      (node (ref "DTR-DSR") (pin "2") (pinfunction "2_2") (pintype "passive"))
      (node (ref "SV1") (pin "5") (pinfunction "5_5") (pintype "passive"))
      (node (ref "U14") (pin "3") (pinfunction "C107/DSR(O)/GPO_C_3") (pintype "output"))
    )
    (net (code "18") (name "GSM-DTR") (class "Default")
      (node (ref "DTR-DSR") (pin "1") (pinfunction "1_1") (pintype "passive"))
      (node (ref "SV1") (pin "3") (pinfunction "3_3") (pintype "passive"))
      (node (ref "U14") (pin "4") (pinfunction "C108/DTR(I)/GPI_E_4") (pintype "input"))
    )
    (net (code "19") (name "GSM-PWRMON") (class "Default")
      (node (ref "J3") (pin "1") (pinfunction "1_1") (pintype "passive"))
      (node (ref "U14") (pin "43") (pinfunction "VAUX/PWRMON_43") (pintype "output"))
    )
    (net (code "20") (name "GSM-RTS") (class "Default")
      (node (ref "RTS-CTS") (pin "2") (pinfunction "2_2") (pintype "passive"))
      (node (ref "SV1") (pin "4") (pinfunction "4_4") (pintype "passive"))
      (node (ref "U14") (pin "5") (pinfunction "C105/RTS(I)/GPI_F_5") (pintype "input"))
    )
    (net (code "21") (name "GSM-RXD1") (class "Default")
      (node (ref "GPS-TXD") (pin "1") (pinfunction "1_1") (pintype "passive"))
      (node (ref "U14") (pin "44") (pinfunction "RXD_AUX(I)_44") (pintype "input"))
    )
    (net (code "22") (name "GSM-TXD1") (class "Default")
      (node (ref "GPS-RXD") (pin "1") (pinfunction "1_1") (pintype "passive"))
      (node (ref "U14") (pin "45") (pinfunction "TXD_AUX(O)_45") (pintype "output"))
    )
    (net (code "23") (name "Net-(ANT1-ANT)") (class "Default")
      (node (ref "ANT1") (pin "A") (pinfunction "ANT_A") (pintype "passive"))
      (node (ref "ANT3") (pin "1") (pinfunction "ANT_1") (pintype "passive"))
      (node (ref "C50") (pin "1") (pinfunction "1_1") (pintype "passive"))
      (node (ref "D3") (pin "1") (pinfunction "C_1") (pintype "passive"))
      (node (ref "L3") (pin "2") (pinfunction "2_2") (pintype "passive"))
    )
    (net (code "24") (name "Net-(C35-Pad1)") (class "Default")
      (node (ref "C35") (pin "1") (pinfunction "1_1") (pintype "passive"))
      (node (ref "R8") (pin "1") (pinfunction "1_1") (pintype "passive"))
    )
    (net (code "25") (name "Net-(C36-Pad2)") (class "Default")
      (node (ref "C36") (pin "2") (pinfunction "2_2") (pintype "passive"))
      (node (ref "R31") (pin "2") (pinfunction "2_2") (pintype "passive"))
    )
    (net (code "26") (name "Net-(D2-A)") (class "Default")
      (node (ref "D2") (pin "P$2") (pinfunction "A_P$2") (pintype "passive"))
      (node (ref "R7") (pin "1") (pinfunction "1_1") (pintype "passive"))
      (node (ref "X1") (pin "9") (pinfunction "9_9") (pintype "passive"))
    )
    (net (code "27") (name "Net-(D14-+)") (class "Default")
      (node (ref "D14") (pin "2") (pinfunction "+_2") (pintype "passive"))
      (node (ref "D4") (pin "2") (pinfunction "+_2") (pintype "passive"))
      (node (ref "R26") (pin "2") (pinfunction "2_2") (pintype "passive"))
      (node (ref "R4") (pin "1") (pinfunction "1_1") (pintype "passive"))
    )
    (net (code "28") (name "Net-(F1-Pad1)") (class "Default")
      (node (ref "F1") (pin "1") (pinfunction "1_1") (pintype "passive"))
      (node (ref "Q5") (pin "1") (pinfunction "A_1") (pintype "passive"))
      (node (ref "Q5") (pin "2") (pinfunction "A_2") (pintype "passive"))
      (node (ref "Q5") (pin "5") (pinfunction "D_5") (pintype "passive"))
      (node (ref "Q5") (pin "6") (pinfunction "D_6") (pintype "passive"))
    )
    (net (code "29") (name "Net-(GPIO1-1)") (class "Default")
      (node (ref "GPIO1") (pin "P$1") (pinfunction "1_P$1") (pintype "bidirectional"))
      (node (ref "U14") (pin "42") (pinfunction "GPIO_01/DVI_WA0_42") (pintype "bidirectional"))
    )
    (net (code "30") (name "Net-(GPIO2-1)") (class "Default")
      (node (ref "GPIO2") (pin "P$1") (pinfunction "1_P$1") (pintype "bidirectional"))
      (node (ref "U14") (pin "41") (pinfunction "GPIO_02/JDR/DVI_RX_41") (pintype "bidirectional"))
    )
    (net (code "31") (name "Net-(GPIO3-1)") (class "Default")
      (node (ref "GPIO3") (pin "P$1") (pinfunction "1_P$1") (pintype "bidirectional"))
      (node (ref "U14") (pin "40") (pinfunction "GPIO_03/DVI_TX_40") (pintype "bidirectional"))
    )
    (net (code "32") (name "Net-(GPIO5-1)") (class "Default")
      (node (ref "GPIO5") (pin "P$1") (pinfunction "1_P$1") (pintype "bidirectional"))
      (node (ref "U14") (pin "29") (pinfunction "GPIO_05/RFTXMON_29") (pintype "bidirectional"))
    )
    (net (code "33") (name "Net-(GPIO6-1)") (class "Default")
      (node (ref "GPIO6") (pin "P$1") (pinfunction "1_P$1") (pintype "bidirectional"))
      (node (ref "U14") (pin "28") (pinfunction "GPIO_06/ALARM_28") (pintype "bidirectional"))
    )
    (net (code "34") (name "Net-(GPIO7-1)") (class "Default")
      (node (ref "GPIO7") (pin "P$1") (pinfunction "1_P$1") (pintype "bidirectional"))
      (node (ref "U14") (pin "27") (pinfunction "GPIO_07/BUZZER_27") (pintype "bidirectional"))
    )
    (net (code "35") (name "Net-(GPIO8-1)") (class "Default")
      (node (ref "GPIO8") (pin "P$1") (pinfunction "1_P$1") (pintype "bidirectional"))
      (node (ref "U14") (pin "26") (pinfunction "GPIO_08/STAT_LED_26") (pintype "bidirectional"))
    )
    (net (code "36") (name "Net-(IC1A-VBAT)") (class "Default")
      (node (ref "IC1") (pin "1") (pinfunction "VBAT_1") (pintype "power_in"))
      (node (ref "JP4") (pin "1") (pinfunction "1_1") (pintype "passive"))
    )
    (net (code "37") (name "Net-(IC1A-VDDA)") (class "Default")
      (node (ref "BEAD1") (pin "1") (pinfunction "1_1") (pintype "passive"))
      (node (ref "C25") (pin "1") (pinfunction "1_1") (pintype "passive"))
      (node (ref "C26") (pin "2") (pinfunction "2_2") (pintype "passive"))
      (node (ref "IC1") (pin "9") (pinfunction "VDDA_9") (pintype "power_in"))
    )
    (net (code "38") (name "Net-(IC1E-PB2)") (class "Default")
      (node (ref "IC1") (pin "20") (pinfunction "PB2_20") (pintype "bidirectional"))
      (node (ref "R5") (pin "1") (pinfunction "1_1") (pintype "passive"))
    )
    (net (code "39") (name "Net-(IC1G-PD0{slash}OSC<=)") (class "Default")
      (node (ref "C56") (pin "2") (pinfunction "2_2") (pintype "passive"))
      (node (ref "IC1") (pin "5") (pinfunction "PD0/OSC<=_5") (pintype "bidirectional"))
      (node (ref "Q4") (pin "1") (pinfunction "1_1") (pintype "passive"))
    )
    (net (code "40") (name "Net-(IC1G-PD1{slash}OSC=>)") (class "Default")
      (node (ref "C57") (pin "1") (pinfunction "1_1") (pintype "passive"))
      (node (ref "IC1") (pin "6") (pinfunction "PD1/OSC=>_6") (pintype "bidirectional"))
      (node (ref "Q4") (pin "2") (pinfunction "2_2") (pintype "passive"))
    )
    (net (code "41") (name "Net-(IC1I-BOOT0)") (class "Default")
      (node (ref "IC1") (pin "44") (pinfunction "BOOT0_44") (pintype "input"))
      (node (ref "JP7") (pin "1") (pinfunction "1_1") (pintype "passive"))
      (node (ref "R25") (pin "2") (pinfunction "2_2") (pintype "passive"))
    )
    (net (code "42") (name "Net-(JP1-Pad2)") (class "Default")
      (node (ref "JP1") (pin "2") (pinfunction "2_2") (pintype "passive"))
      (node (ref "R32") (pin "2") (pinfunction "2_2") (pintype "passive"))
    )
    (net (code "43") (name "Net-(L1-1)") (class "Default")
      (node (ref "L1") (pin "P$1") (pinfunction "1_P$1") (pintype "passive"))
      (node (ref "U8") (pin "7") (pinfunction "SW_7") (pintype "passive"))
    )
    (net (code "44") (name "Net-(LED1-C)") (class "Default")
      (node (ref "LED1") (pin "K") (pinfunction "C_K") (pintype "passive"))
      (node (ref "LED2") (pin "A") (pinfunction "A_A") (pintype "passive"))
      (node (ref "R6") (pin "1") (pinfunction "1_1") (pintype "passive"))
    )
    (net (code "45") (name "Net-(Q1-D)") (class "Default")
      (node (ref "C19") (pin "1") (pinfunction "1_1") (pintype "passive"))
      (node (ref "C45") (pin "1") (pinfunction "1_1") (pintype "passive"))
      (node (ref "Q1") (pin "3") (pinfunction "D_3") (pintype "passive"))
      (node (ref "U14") (pin "37") (pinfunction "VBATT_PA_37") (pintype "passive"))
      (node (ref "U14") (pin "38") (pinfunction "VBATT_38") (pintype "passive"))
    )
    (net (code "46") (name "Net-(Q1-G)") (class "Default")
      (node (ref "Q1") (pin "1") (pinfunction "G_1") (pintype "passive"))
      (node (ref "Q2") (pin "3") (pinfunction "C_3") (pintype "passive"))
      (node (ref "R1") (pin "1") (pinfunction "1_1") (pintype "passive"))
    )
    (net (code "47") (name "Net-(Q2-B)") (class "Default")
      (node (ref "Q2") (pin "1") (pinfunction "B_1") (pintype "passive"))
      (node (ref "R2") (pin "2") (pinfunction "2_2") (pintype "passive"))
      (node (ref "R3") (pin "1") (pinfunction "1_1") (pintype "passive"))
    )
    (net (code "48") (name "Net-(Q5-G)") (class "Default")
      (node (ref "C43") (pin "1") (pinfunction "1_1") (pintype "passive"))
      (node (ref "Q5") (pin "4") (pinfunction "G_4") (pintype "passive"))
      (node (ref "R28") (pin "2") (pinfunction "2_2") (pintype "passive"))
      (node (ref "R29") (pin "2") (pinfunction "2_2") (pintype "passive"))
    )
    (net (code "49") (name "Net-(U2-IO)") (class "Default")
      (node (ref "JS4") (pin "1") (pinfunction "1_1") (pintype "passive"))
      (node (ref "U2") (pin "3") (pinfunction "IO_3") (pintype "bidirectional"))
    )
    (net (code "50") (name "Net-(U5-AVDD)") (class "Default")
      (node (ref "BEAD2") (pin "1") (pinfunction "1_1") (pintype "passive"))
      (node (ref "C5") (pin "1") (pinfunction "1_1") (pintype "passive"))
      (node (ref "C6") (pin "1") (pinfunction "1_1") (pintype "passive"))
      (node (ref "C7") (pin "1") (pinfunction "1_1") (pintype "passive"))
      (node (ref "C8") (pin "1") (pinfunction "1_1") (pintype "passive"))
      (node (ref "U5") (pin "1") (pinfunction "DVDD_IO_1") (pintype "power_in"))
      (node (ref "U5") (pin "6") (pinfunction "AVDD_6") (pintype "power_in"))
      (node (ref "U5") (pin "7") (pinfunction "CS_7") (pintype "input"))
    )
    (net (code "51") (name "Net-(U8-FB)") (class "Default")
      (node (ref "C14") (pin "1") (pinfunction "1_1") (pintype "passive"))
      (node (ref "R10") (pin "1") (pinfunction "1_1") (pintype "passive"))
      (node (ref "R9") (pin "1") (pinfunction "1_1") (pintype "passive"))
      (node (ref "U8") (pin "3") (pinfunction "FB_3") (pintype "passive"))
    )
    (net (code "52") (name "Net-(U9-EN)") (class "Default")
      (node (ref "J1") (pin "1") (pinfunction "1_1") (pintype "passive"))
      (node (ref "J2") (pin "2") (pinfunction "2_2") (pintype "passive"))
      (node (ref "R12") (pin "1") (pinfunction "1_1") (pintype "passive"))
      (node (ref "U9") (pin "3") (pinfunction "EN_3") (pintype "input"))
    )
    (net (code "53") (name "Net-(U9-OUT)") (class "Default")
      (node (ref "C16") (pin "1") (pinfunction "1_1") (pintype "passive"))
      (node (ref "C17") (pin "1") (pinfunction "1_1") (pintype "passive"))
      (node (ref "C27") (pin "1") (pinfunction "1_1") (pintype "passive"))
      (node (ref "C51") (pin "1") (pinfunction "1_1") (pintype "passive"))
      (node (ref "L3") (pin "1") (pinfunction "1_1") (pintype "passive"))
      (node (ref "U15") (pin "23") (pinfunction "VCC_IN_23") (pintype "passive"))
      (node (ref "U15") (pin "9") (pinfunction "VCC_IN_9") (pintype "passive"))
      (node (ref "U9") (pin "5") (pinfunction "OUT_5") (pintype "passive"))
    )
    (net (code "54") (name "Net-(U14-RESET)") (class "Default")
      (node (ref "GSM-RESET") (pin "2") (pinfunction "2_2") (pintype "passive"))
      (node (ref "U14") (pin "47") (pinfunction "RESET_47") (pintype "input"))
    )
    (net (code "55") (name "Net-(U15-RF_IN)") (class "Default")
      (node (ref "C50") (pin "2") (pinfunction "2_2") (pintype "passive"))
      (node (ref "U15") (pin "11") (pinfunction "RF_IN_11") (pintype "passive"))
    )
    (net (code "56") (name "Net-(U15-RX)") (class "Default")
      (node (ref "JP2") (pin "3") (pinfunction "3_3") (pintype "passive"))
      (node (ref "U15") (pin "21") (pinfunction "RX_21") (pintype "input"))
    )
    (net (code "57") (name "Net-(U15-RX2)") (class "Default")
      (node (ref "JP2") (pin "1") (pinfunction "1_1") (pintype "passive"))
      (node (ref "U15") (pin "15") (pinfunction "RX2_15") (pintype "input"))
    )
    (net (code "58") (name "Net-(U15-TX)") (class "Default")
      (node (ref "JP6") (pin "3") (pinfunction "3_3") (pintype "passive"))
      (node (ref "U15") (pin "20") (pinfunction "TX_20") (pintype "output"))
    )
    (net (code "59") (name "Net-(U15-TX2{slash}BOOT)") (class "Default")
      (node (ref "JP6") (pin "1") (pinfunction "1_1") (pintype "passive"))
      (node (ref "U15") (pin "14") (pinfunction "TX2/BOOT_14") (pintype "output"))
    )
    (net (code "60") (name "Net-(U15-VDDUSB)") (class "Default")
      (node (ref "R13") (pin "1") (pinfunction "1_1") (pintype "passive"))
      (node (ref "U15") (pin "7") (pinfunction "VDDUSB_7") (pintype "bidirectional"))
    )
    (net (code "61") (name "PA0.SENS-D1") (class "Default")
      (node (ref "C13") (pin "1") (pinfunction "1_1") (pintype "passive"))
      (node (ref "D4") (pin "3") (pinfunction "S_3") (pintype "passive"))
      (node (ref "IC1") (pin "10") (pinfunction "PA0_10") (pintype "bidirectional"))
      (node (ref "R27") (pin "2") (pinfunction "2_2") (pintype "passive"))
      (node (ref "SEND-D1") (pin "P$1") (pinfunction "1_P$1") (pintype "bidirectional"))
    )
    (net (code "62") (name "PA1.SENS-A1") (class "Default")
      (node (ref "C40") (pin "1") (pinfunction "1_1") (pintype "passive"))
      (node (ref "D14") (pin "3") (pinfunction "S_3") (pintype "passive"))
      (node (ref "IC1") (pin "11") (pinfunction "PA1_11") (pintype "bidirectional"))
      (node (ref "R41") (pin "2") (pinfunction "2_2") (pintype "passive"))
      (node (ref "R42") (pin "2") (pinfunction "2_2") (pintype "passive"))
      (node (ref "SEND-A1") (pin "P$1") (pinfunction "1_P$1") (pintype "bidirectional"))
    )
    (net (code "63") (name "PA2.USART2-TX") (class "Default")
      (node (ref "IC1") (pin "12") (pinfunction "PA2_12") (pintype "bidirectional"))
      (node (ref "JP3") (pin "1") (pinfunction "1_1") (pintype "passive"))
    )
    (net (code "64") (name "PA3.USART2-RX") (class "Default")
      (node (ref "IC1") (pin "13") (pinfunction "PA3_13") (pintype "bidirectional"))
      (node (ref "JP3") (pin "2") (pinfunction "2_2") (pintype "passive"))
    )
    (net (code "65") (name "PA4") (class "Default")
      (node (ref "IC1") (pin "14") (pinfunction "PA4_14") (pintype "bidirectional"))
      (node (ref "JP5") (pin "3") (pinfunction "3_3") (pintype "passive"))
    )
    (net (code "66") (name "PA5") (class "Default")
      (node (ref "IC1") (pin "15") (pinfunction "PA5_15") (pintype "bidirectional"))
      (node (ref "JP5") (pin "4") (pinfunction "4_4") (pintype "passive"))
    )
    (net (code "67") (name "PA6") (class "Default")
      (node (ref "IC1") (pin "16") (pinfunction "PA6_16") (pintype "bidirectional"))
      (node (ref "JP5") (pin "5") (pinfunction "5_5") (pintype "passive"))
    )
    (net (code "68") (name "PA7") (class "Default")
      (node (ref "IC1") (pin "17") (pinfunction "PA7_17") (pintype "bidirectional"))
      (node (ref "JP5") (pin "6") (pinfunction "6_6") (pintype "passive"))
    )
    (net (code "69") (name "PA9.GSM-TXD(I)") (class "Default")
      (node (ref "IC1") (pin "30") (pinfunction "PA9_30") (pintype "bidirectional"))
      (node (ref "SV1") (pin "6") (pinfunction "6_6") (pintype "passive"))
      (node (ref "U14") (pin "7") (pinfunction "C103/TXD(I)_7") (pintype "input"))
    )
    (net (code "70") (name "PA10.GSM-RXD(O)") (class "Default")
      (node (ref "IC1") (pin "31") (pinfunction "PA10_31") (pintype "bidirectional"))
      (node (ref "SV1") (pin "7") (pinfunction "7_7") (pintype "passive"))
      (node (ref "U14") (pin "8") (pinfunction "C104/RXD(O)_8") (pintype "output"))
    )
    (net (code "71") (name "PA11.GSM-PWR") (class "Default")
      (node (ref "IC1") (pin "32") (pinfunction "PA11_32") (pintype "bidirectional"))
      (node (ref "R3") (pin "2") (pinfunction "2_2") (pintype "passive"))
    )
    (net (code "72") (name "PA12.GPS-PWR") (class "Default")
      (node (ref "IC1") (pin "33") (pinfunction "PA12_33") (pintype "bidirectional"))
      (node (ref "J1") (pin "2") (pinfunction "2_2") (pintype "passive"))
    )
    (net (code "73") (name "PA15.#CAN-EN") (class "Default")
      (node (ref "IC1") (pin "38") (pinfunction "PA15_38") (pintype "bidirectional"))
      (node (ref "R33") (pin "2") (pinfunction "2_2") (pintype "passive"))
      (node (ref "U6") (pin "8") (pinfunction "RS_8") (pintype "bidirectional"))
    )
    (net (code "74") (name "PB0.RELAY-ON") (class "Default")
      (node (ref "IC1") (pin "29") (pinfunction "PA8_29") (pintype "bidirectional"))
      (node (ref "R29") (pin "1") (pinfunction "1_1") (pintype "passive"))
      (node (ref "RELAY") (pin "P$1") (pinfunction "1_P$1") (pintype "bidirectional"))
    )
    (net (code "75") (name "PB5.ACC-INT1") (class "Default")
      (node (ref "IC1") (pin "41") (pinfunction "PB5_41") (pintype "bidirectional"))
      (node (ref "U5") (pin "8") (pinfunction "INT1/RDY_8") (pintype "output"))
    )
    (net (code "76") (name "PB6.ACC-SCL") (class "Default")
      (node (ref "IC1") (pin "42") (pinfunction "PB6_42") (pintype "bidirectional"))
      (node (ref "R46") (pin "1") (pinfunction "1_1") (pintype "passive"))
      (node (ref "U5") (pin "14") (pinfunction "SCL/SPC_14") (pintype "input"))
    )
    (net (code "77") (name "PB7.ACC-SDA") (class "Default")
      (node (ref "IC1") (pin "43") (pinfunction "PB7_43") (pintype "bidirectional"))
      (node (ref "R30") (pin "2") (pinfunction "2_2") (pintype "passive"))
      (node (ref "U5") (pin "13") (pinfunction "SDA/SDI/SDO_13") (pintype "bidirectional"))
    )
    (net (code "78") (name "PB8.CAN-RX") (class "Default")
      (node (ref "IC1") (pin "45") (pinfunction "PB8_45") (pintype "bidirectional"))
      (node (ref "U6") (pin "4") (pinfunction "RXD_4") (pintype "bidirectional"))
    )
    (net (code "79") (name "PB9.CAN-TX") (class "Default")
      (node (ref "IC1") (pin "46") (pinfunction "PB9_46") (pintype "bidirectional"))
      (node (ref "U6") (pin "1") (pinfunction "TXD_1") (pintype "bidirectional"))
    )
    (net (code "80") (name "PB10.GPS-TX") (class "Default")
      (node (ref "GPS-RXD") (pin "2") (pinfunction "2_2") (pintype "passive"))
      (node (ref "IC1") (pin "21") (pinfunction "PB10_21") (pintype "bidirectional"))
      (node (ref "JP2") (pin "2") (pinfunction "2_2") (pintype "passive"))
    )
    (net (code "81") (name "PB11.GPS-RX") (class "Default")
      (node (ref "GPS-TXD") (pin "2") (pinfunction "2_2") (pintype "passive"))
      (node (ref "IC1") (pin "22") (pinfunction "PB11_22") (pintype "bidirectional"))
      (node (ref "JP6") (pin "2") (pinfunction "2_2") (pintype "passive"))
    )
    (net (code "82") (name "RELAY") (class "Default")
      (node (ref "F1") (pin "2") (pinfunction "2_2") (pintype "passive"))
      (node (ref "X1") (pin "8") (pinfunction "8_8") (pintype "passive"))
    )
    (net (code "83") (name "RESET") (class "Default")
      (node (ref "C42") (pin "1") (pinfunction "1_1") (pintype "passive"))
      (node (ref "IC1") (pin "7") (pinfunction "NRST_7") (pintype "input"))
      (node (ref "JP3") (pin "4") (pinfunction "4_4") (pintype "passive"))
      (node (ref "R43") (pin "1") (pinfunction "1_1") (pintype "passive"))
    )
    (net (code "84") (name "SIMCLK") (class "Default")
      (node (ref "C3") (pin "2") (pinfunction "2_2") (pintype "passive"))
      (node (ref "U14") (pin "11") (pinfunction "SIMCLK_11") (pintype "output"))
      (node (ref "U2") (pin "6") (pinfunction "CLK_6") (pintype "input"))
      (node (ref "U4") (pin "3") (pinfunction "CLK_3") (pintype "input"))
    )
    (net (code "85") (name "SIMIO") (class "Default")
      (node (ref "C2") (pin "1") (pinfunction "1_1") (pintype "passive"))
      (node (ref "JS4") (pin "2") (pinfunction "2_2") (pintype "passive"))
      (node (ref "U14") (pin "12") (pinfunction "SIMIO_12") (pintype "bidirectional"))
      (node (ref "U4") (pin "6") (pinfunction "IO_6") (pintype "bidirectional"))
    )
    (net (code "86") (name "SIMRST") (class "Default")
      (node (ref "C18") (pin "2") (pinfunction "2_2") (pintype "passive"))
      (node (ref "U14") (pin "10") (pinfunction "SIMRST_10") (pintype "output"))
      (node (ref "U2") (pin "7") (pinfunction "RST_7") (pintype "input"))
      (node (ref "U4") (pin "2") (pinfunction "RST_2") (pintype "input"))
    )
    (net (code "87") (name "SIMVCC") (class "Default")
      (node (ref "C4") (pin "2") (pinfunction "2_2") (pintype "passive"))
      (node (ref "U14") (pin "9") (pinfunction "SIMVCC_9") (pintype "passive"))
      (node (ref "U2") (pin "8") (pinfunction "VCC_8") (pintype "passive"))
      (node (ref "U4") (pin "1") (pinfunction "VCC_1") (pintype "passive"))
    )
    (net (code "88") (name "SWCLK") (class "Default")
      (node (ref "IC1") (pin "19") (pinfunction "PB1_19") (pintype "bidirectional"))
      (node (ref "IC1") (pin "37") (pinfunction "PA14_37") (pintype "bidirectional"))
      (node (ref "JP3") (pin "5") (pinfunction "5_5") (pintype "passive"))
      (node (ref "R38") (pin "2") (pinfunction "2_2") (pintype "passive"))
    )
    (net (code "89") (name "SWDIO") (class "Default")
      (node (ref "IC1") (pin "34") (pinfunction "PA13_34") (pintype "bidirectional"))
      (node (ref "JP3") (pin "6") (pinfunction "6_6") (pintype "passive"))
    )
    (net (code "90") (name "VDC") (class "Default")
      (node (ref "C1") (pin "2") (pinfunction "2_2") (pintype "passive"))
      (node (ref "D5") (pin "3") (pinfunction "S_3") (pintype "passive"))
      (node (ref "IC1") (pin "18") (pinfunction "PB0_18") (pintype "bidirectional"))
      (node (ref "R11") (pin "2") (pinfunction "2_2") (pintype "passive"))
      (node (ref "R7") (pin "2") (pinfunction "2_2") (pintype "passive"))
    )
    (net (code "91") (name "VMAIN(4V)") (class "Default")
      (node (ref "C10") (pin "1") (pinfunction "1_1") (pintype "passive"))
      (node (ref "C14") (pin "2") (pinfunction "2_2") (pintype "passive"))
      (node (ref "C15") (pin "2") (pinfunction "2_2") (pintype "passive"))
      (node (ref "C30") (pin "1") (pinfunction "1_1") (pintype "passive"))
      (node (ref "C44") (pin "2") (pinfunction "2_2") (pintype "passive"))
      (node (ref "C46") (pin "+") (pinfunction "+_+") (pintype "passive"))
      (node (ref "C52") (pin "2") (pinfunction "2_2") (pintype "passive"))
      (node (ref "C9") (pin "1") (pinfunction "1_1") (pintype "passive"))
      (node (ref "L1") (pin "P$2") (pinfunction "2_P$2") (pintype "passive"))
      (node (ref "Q1") (pin "2") (pinfunction "S_2") (pintype "passive"))
      (node (ref "R1") (pin "2") (pinfunction "2_2") (pintype "passive"))
      (node (ref "R9") (pin "2") (pinfunction "2_2") (pintype "passive"))
      (node (ref "U13") (pin "1") (pinfunction "IN_1") (pintype "passive"))
      (node (ref "U13") (pin "3") (pinfunction "EN_3") (pintype "input"))
      (node (ref "U9") (pin "1") (pinfunction "IN_1") (pintype "passive"))
    )
    (net (code "92") (name "unconnected-(U2-NC-Pad2)") (class "Default")
      (node (ref "U2") (pin "2") (pinfunction "NC_2") (pintype "no_connect"))
    )
    (net (code "93") (name "unconnected-(U4-NC-Pad5)") (class "Default")
      (node (ref "U4") (pin "5") (pinfunction "NC_5") (pintype "no_connect"))
    )
    (net (code "94") (name "unconnected-(U5-INT2-Pad9)") (class "Default")
      (node (ref "U5") (pin "9") (pinfunction "INT2_9") (pintype "output"))
    )
    (net (code "95") (name "unconnected-(U5-SDO-Pad12)") (class "Default")
      (node (ref "U5") (pin "12") (pinfunction "SDO_12") (pintype "tri_state"))
    )
    (net (code "96") (name "unconnected-(U6-VREF-Pad5)") (class "Default")
      (node (ref "U6") (pin "5") (pinfunction "VREF_5") (pintype "bidirectional"))
    )
    (net (code "97") (name "unconnected-(U9-NC-Pad4)") (class "Default")
      (node (ref "U9") (pin "4") (pinfunction "NC_4") (pintype "no_connect"))
    )
    (net (code "98") (name "unconnected-(U13-NC-Pad4)") (class "Default")
      (node (ref "U13") (pin "4") (pinfunction "NC_4") (pintype "no_connect"))
    )
    (net (code "99") (name "unconnected-(U14-ADC_IN1-Pad13)") (class "Default")
      (node (ref "U14") (pin "13") (pinfunction "ADC_IN1_13") (pintype "input"))
    )
    (net (code "100") (name "unconnected-(U14-ADC_IN2-Pad14)") (class "Default")
      (node (ref "U14") (pin "14") (pinfunction "ADC_IN2_14") (pintype "input"))
    )
    (net (code "101") (name "unconnected-(U14-C109{slash}DCD{slash}GPO_A-Pad1)") (class "Default")
      (node (ref "U14") (pin "1") (pinfunction "C109/DCD/GPO_A_1") (pintype "output"))
    )
    (net (code "102") (name "unconnected-(U14-C125{slash}RING{slash}GPO_B-Pad2)") (class "Default")
      (node (ref "U14") (pin "2") (pinfunction "C125/RING/GPO_B_2") (pintype "output"))
    )
    (net (code "103") (name "unconnected-(U14-DAC_OUT-Pad15)") (class "Default")
      (node (ref "U14") (pin "15") (pinfunction "DAC_OUT_15") (pintype "output"))
    )
    (net (code "104") (name "unconnected-(U14-VRTC-Pad30)") (class "Default")
      (node (ref "U14") (pin "30") (pinfunction "VRTC_30") (pintype "passive"))
    )
    (net (code "105") (name "unconnected-(U15-1PPS-Pad3)") (class "Default")
      (node (ref "U15") (pin "3") (pinfunction "1PPS_3") (pintype "output"))
    )
    (net (code "106") (name "unconnected-(U15-CAN0RX-Pad2)") (class "Default")
      (node (ref "U15") (pin "2") (pinfunction "CAN0RX_2") (pintype "input"))
    )
    (net (code "107") (name "unconnected-(U15-CAN0TX-Pad1)") (class "Default")
      (node (ref "U15") (pin "1") (pinfunction "CAN0TX_1") (pintype "output"))
    )
    (net (code "108") (name "unconnected-(U15-EXT_INT-Pad4)") (class "Default")
      (node (ref "U15") (pin "4") (pinfunction "EXT_INT_4") (pintype "bidirectional"))
    )
    (net (code "109") (name "unconnected-(U15-NC-Pad8)") (class "Default")
      (node (ref "U15") (pin "8") (pinfunction "NC_8") (pintype "no_connect"))
    )
    (net (code "110") (name "unconnected-(U15-NC-Pad16)") (class "Default")
      (node (ref "U15") (pin "16") (pinfunction "NC_16") (pintype "no_connect"))
    )
    (net (code "111") (name "unconnected-(U15-NC-Pad17)") (class "Default")
      (node (ref "U15") (pin "17") (pinfunction "NC_17") (pintype "no_connect"))
    )
    (net (code "112") (name "unconnected-(U15-SCL2-Pad19)") (class "Default")
      (node (ref "U15") (pin "19") (pinfunction "SCL2_19") (pintype "bidirectional"))
    )
    (net (code "113") (name "unconnected-(U15-SDA2-Pad18)") (class "Default")
      (node (ref "U15") (pin "18") (pinfunction "SDA2_18") (pintype "bidirectional"))
    )
    (net (code "114") (name "unconnected-(U15-USB_DM-Pad5)") (class "Default")
      (node (ref "U15") (pin "5") (pinfunction "USB_DM_5") (pintype "bidirectional"))
    )
    (net (code "115") (name "unconnected-(U15-USB_DP-Pad6)") (class "Default")
      (node (ref "U15") (pin "6") (pinfunction "USB_DP_6") (pintype "bidirectional"))
    )
    (net (code "116") (name "unconnected-(U15-VBAT-Pad22)") (class "Default")
      (node (ref "U15") (pin "22") (pinfunction "VBAT_22") (pintype "passive"))
    )
    (net (code "117") (name "unconnected-(X1-Pad7)") (class "Default")
      (node (ref "X1") (pin "7") (pinfunction "7_7") (pintype "passive"))
    )
  )
)
